# uJOVE7.net
KiCad netlist of a schematic drawn in EAGLE
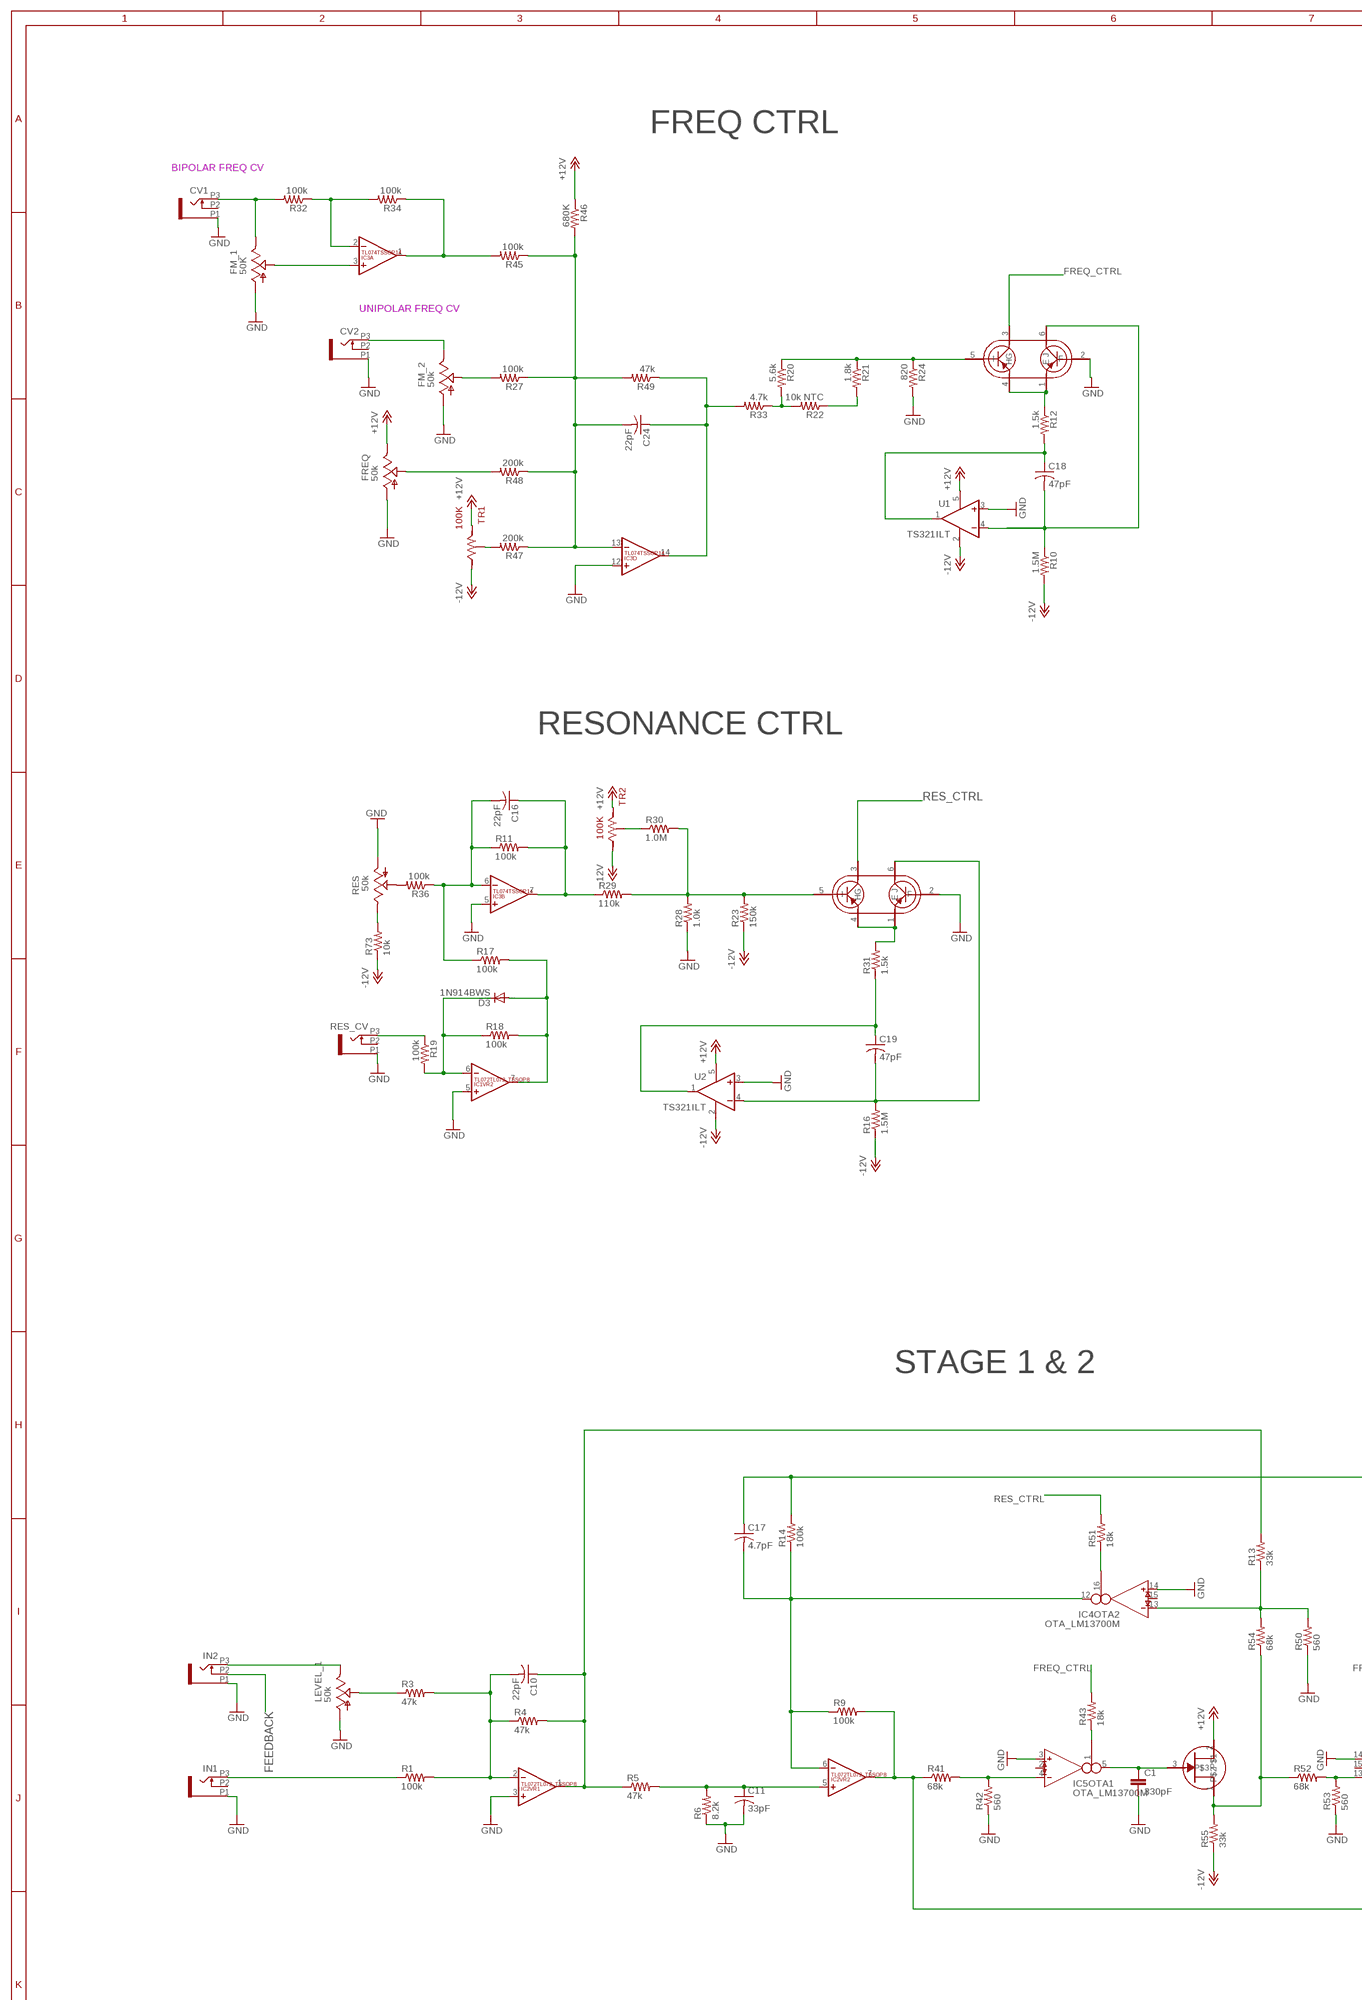
[diagram p0: schematic, sheet 1, part 1 of 3]
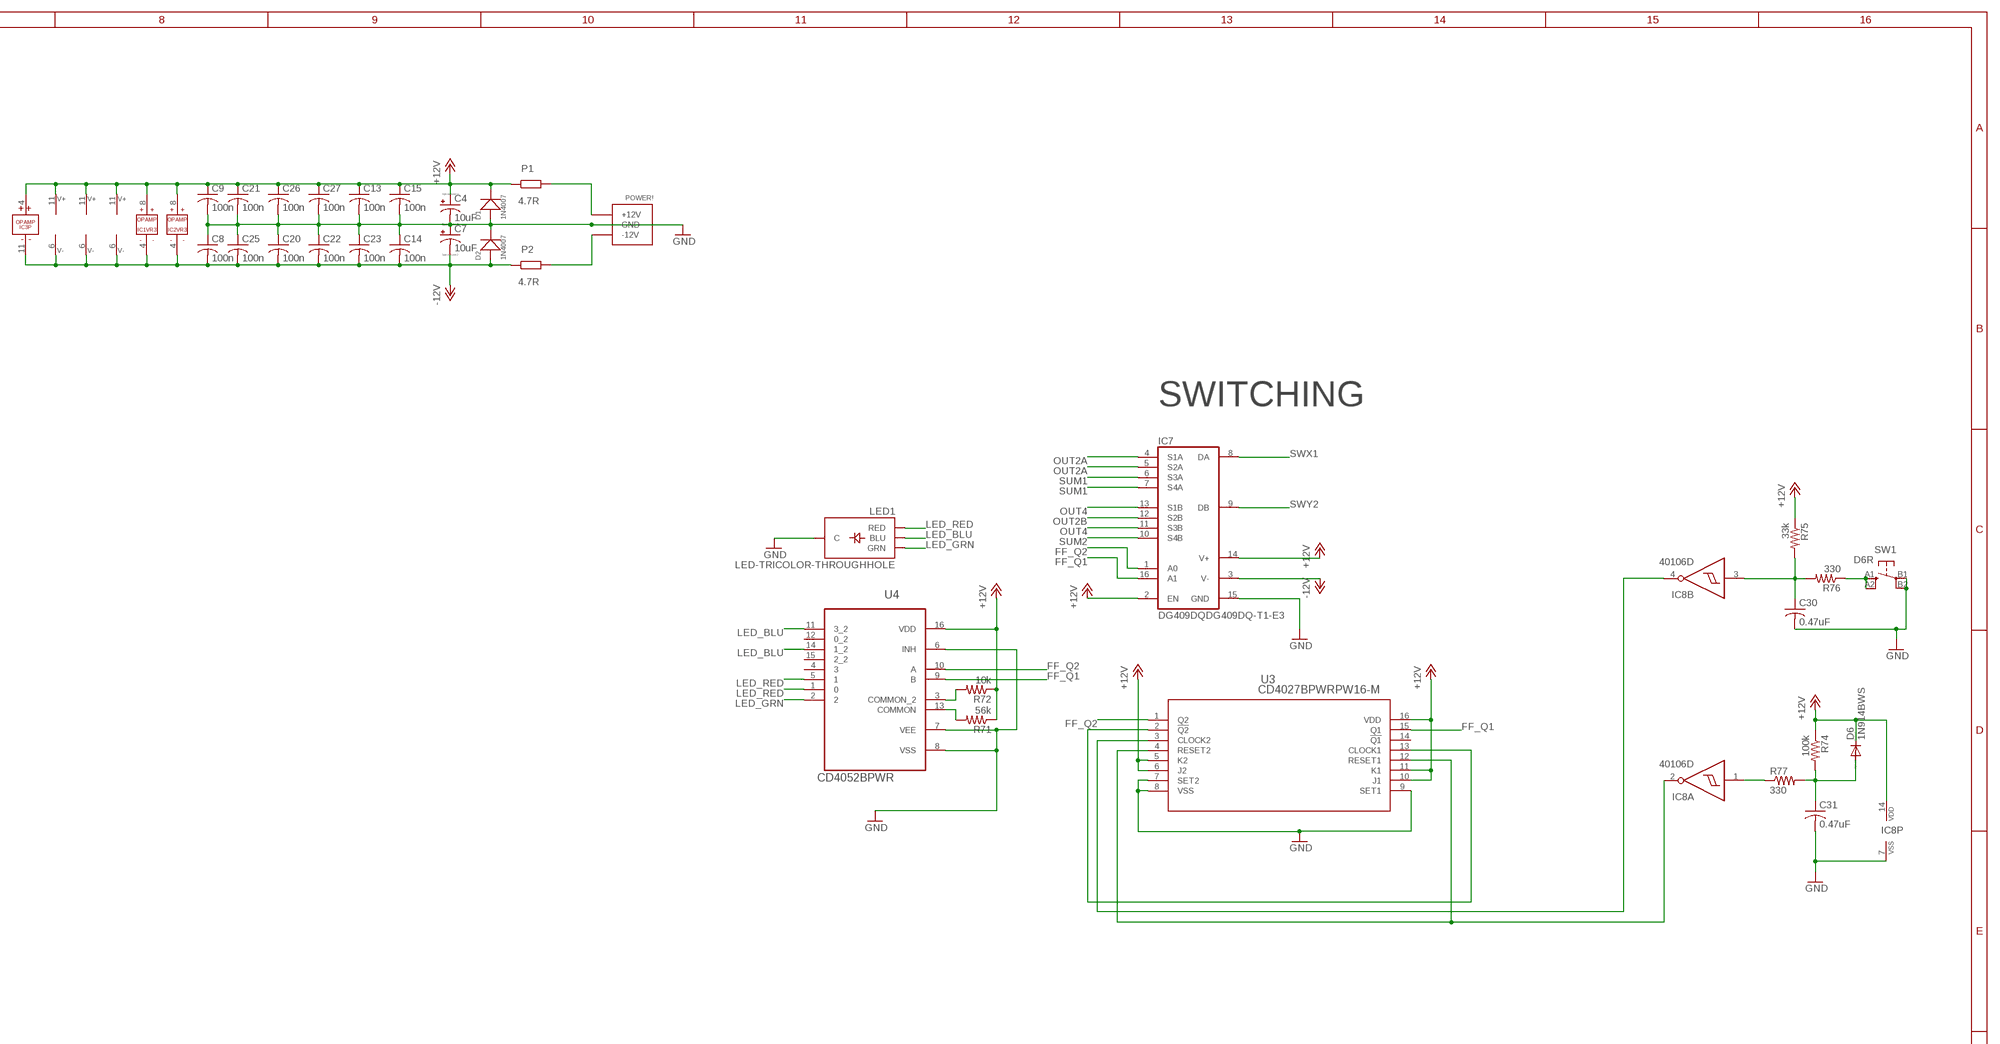
[diagram p1: schematic, sheet 1, part 2 of 3]
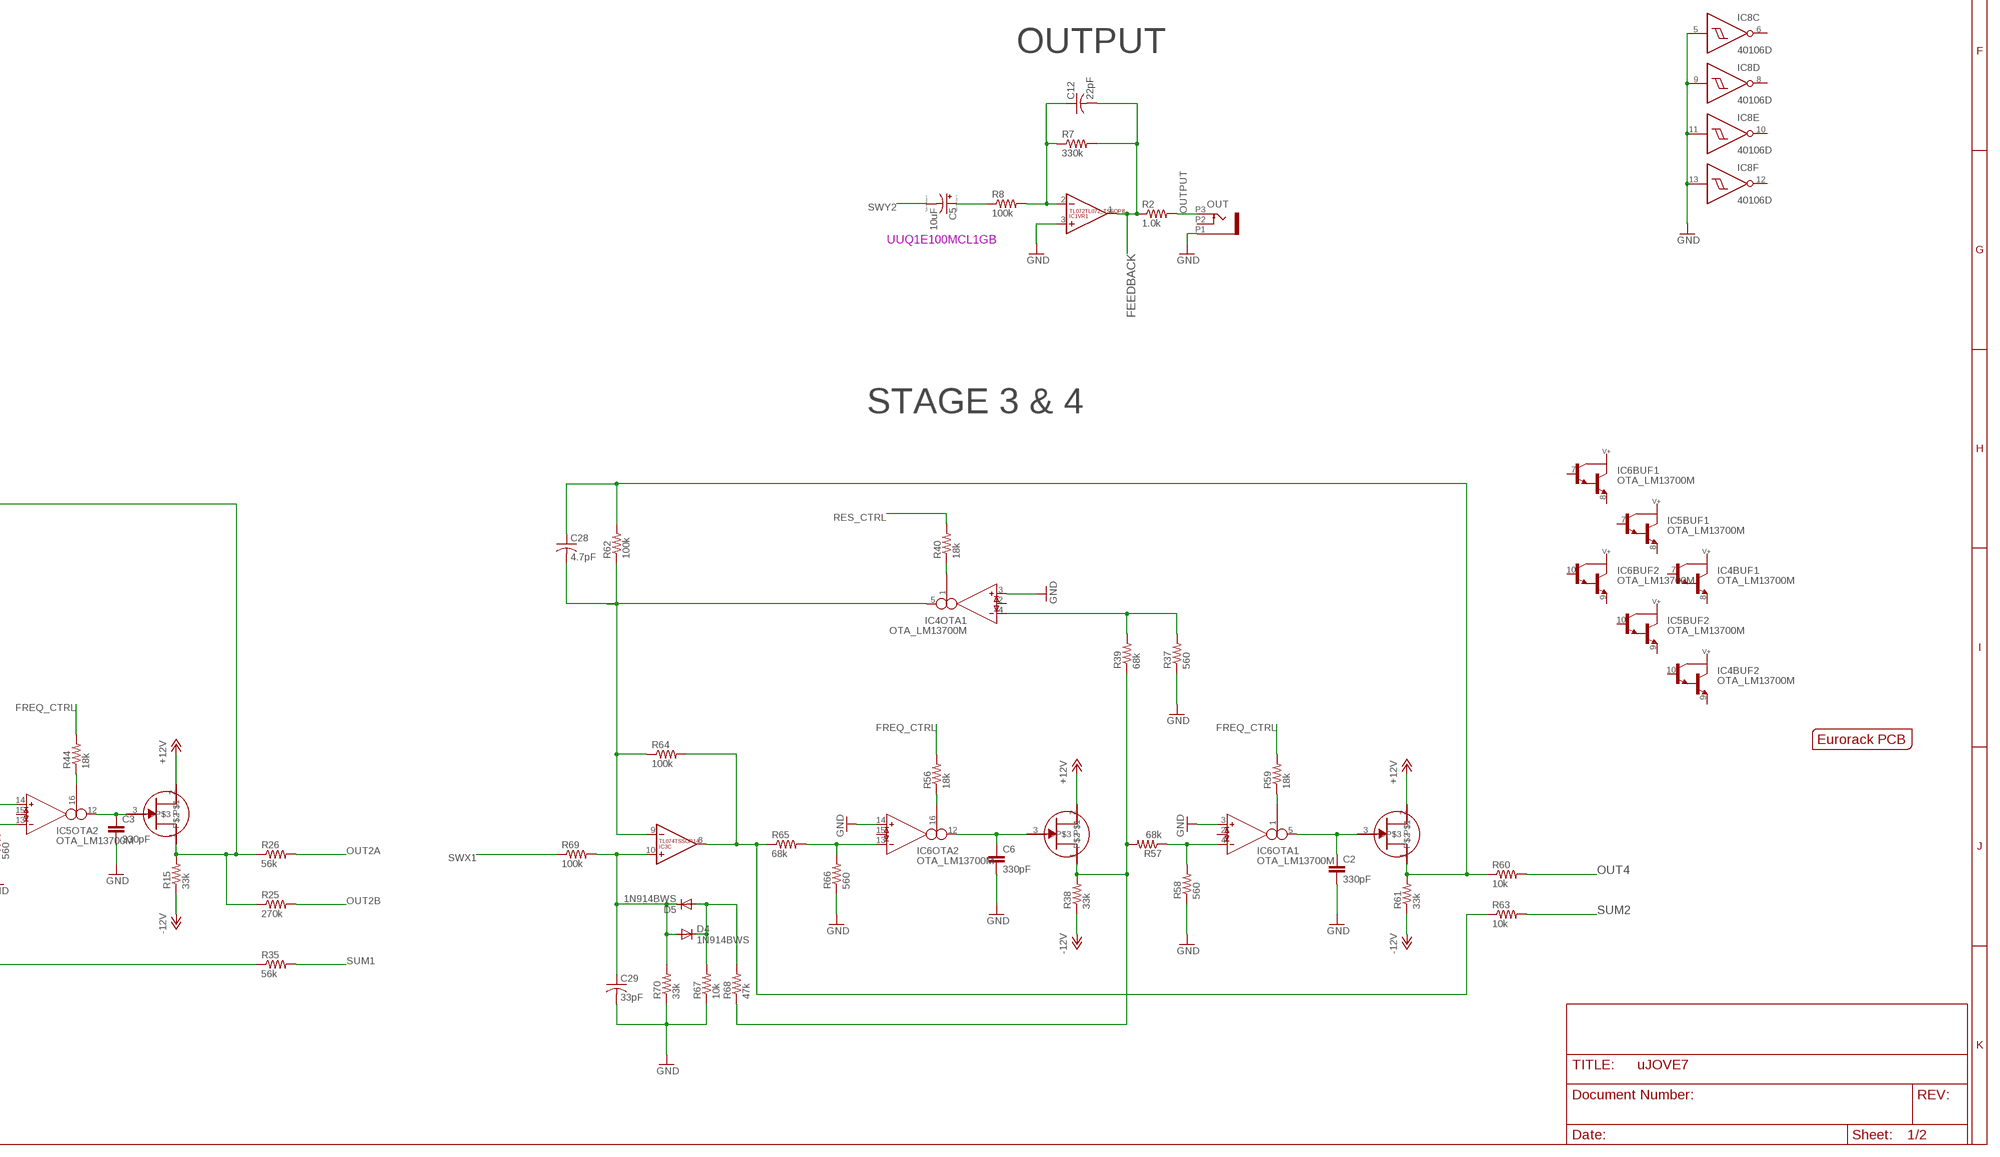
[diagram p2: schematic, sheet 1, part 3 of 3]

(export (version "E")
  (design (tool "Eeschema 10.0.6"))
  (components
    (comp (ref "C1")
      (value "330pF")
      (footprint "eagle-import:C5B5")
      (libsource (lib "eagle-import") (part "C5/5"))
    )
    (comp (ref "C2")
      (value "330pF")
      (footprint "eagle-import:C5B5")
      (libsource (lib "eagle-import") (part "C5/5"))
    )
    (comp (ref "C3")
      (value "330pF")
      (footprint "eagle-import:C5B5")
      (libsource (lib "eagle-import") (part "C5/5"))
    )
    (comp (ref "C4")
      (value "10uF")
      (footprint "eagle-import:PANASONIC_C")
      (libsource (lib "eagle-import") (part "CPOL-USC"))
    )
    (comp (ref "C5")
      (value "10uF")
      (footprint "eagle-import:PANASONIC_C")
      (libsource (lib "eagle-import") (part "CPOL-USC"))
    )
    (comp (ref "C6")
      (value "330pF")
      (footprint "eagle-import:C5B5")
      (libsource (lib "eagle-import") (part "C5/5"))
    )
    (comp (ref "C7")
      (value "10uF")
      (footprint "eagle-import:PANASONIC_C")
      (libsource (lib "eagle-import") (part "CPOL-USC"))
    )
    (comp (ref "C8")
      (value "100n")
      (footprint "eagle-import:C0603")
      (libsource (lib "eagle-import") (part "C-USC0603"))
    )
    (comp (ref "C9")
      (value "100n")
      (footprint "eagle-import:C0603")
      (libsource (lib "eagle-import") (part "C-USC0603"))
    )
    (comp (ref "C10")
      (value "22pF")
      (footprint "eagle-import:C0603")
      (libsource (lib "eagle-import") (part "C-USC0603"))
    )
    (comp (ref "C11")
      (value "33pF")
      (footprint "eagle-import:C0603")
      (libsource (lib "eagle-import") (part "C-USC0603"))
    )
    (comp (ref "C12")
      (value "22pF")
      (footprint "eagle-import:C0603")
      (libsource (lib "eagle-import") (part "C-USC0603"))
    )
    (comp (ref "C13")
      (value "100n")
      (footprint "eagle-import:C0603")
      (libsource (lib "eagle-import") (part "C-USC0603"))
    )
    (comp (ref "C14")
      (value "100n")
      (footprint "eagle-import:C0603")
      (libsource (lib "eagle-import") (part "C-USC0603"))
    )
    (comp (ref "C15")
      (value "100n")
      (footprint "eagle-import:C0603")
      (libsource (lib "eagle-import") (part "C-USC0603"))
    )
    (comp (ref "C16")
      (value "22pF")
      (footprint "eagle-import:C0603")
      (libsource (lib "eagle-import") (part "C-USC0603"))
    )
    (comp (ref "C17")
      (value "4.7pF")
      (footprint "eagle-import:C0603")
      (libsource (lib "eagle-import") (part "C-USC0603"))
    )
    (comp (ref "C18")
      (value "47pF")
      (footprint "eagle-import:C0603")
      (libsource (lib "eagle-import") (part "C-USC0603"))
    )
    (comp (ref "C19")
      (value "47pF")
      (footprint "eagle-import:C0603")
      (libsource (lib "eagle-import") (part "C-USC0603"))
    )
    (comp (ref "C20")
      (value "100n")
      (footprint "eagle-import:C0603")
      (libsource (lib "eagle-import") (part "C-USC0603"))
    )
    (comp (ref "C21")
      (value "100n")
      (footprint "eagle-import:C0603")
      (libsource (lib "eagle-import") (part "C-USC0603"))
    )
    (comp (ref "C22")
      (value "100n")
      (footprint "eagle-import:C0603")
      (libsource (lib "eagle-import") (part "C-USC0603"))
    )
    (comp (ref "C23")
      (value "100n")
      (footprint "eagle-import:C0603")
      (libsource (lib "eagle-import") (part "C-USC0603"))
    )
    (comp (ref "C24")
      (value "22pF")
      (footprint "eagle-import:C0603")
      (libsource (lib "eagle-import") (part "C-USC0603"))
    )
    (comp (ref "C25")
      (value "100n")
      (footprint "eagle-import:C0603")
      (libsource (lib "eagle-import") (part "C-USC0603"))
    )
    (comp (ref "C26")
      (value "100n")
      (footprint "eagle-import:C0603")
      (libsource (lib "eagle-import") (part "C-USC0603"))
    )
    (comp (ref "C27")
      (value "100n")
      (footprint "eagle-import:C0603")
      (libsource (lib "eagle-import") (part "C-USC0603"))
    )
    (comp (ref "C28")
      (value "4.7pF")
      (footprint "eagle-import:C0603")
      (libsource (lib "eagle-import") (part "C-USC0603"))
    )
    (comp (ref "C29")
      (value "33pF")
      (footprint "eagle-import:C0603")
      (libsource (lib "eagle-import") (part "C-USC0603"))
    )
    (comp (ref "C30")
      (value "0.47uF")
      (footprint "eagle-import:C0603")
      (libsource (lib "eagle-import") (part "C-USC0603"))
    )
    (comp (ref "C31")
      (value "0.47uF")
      (footprint "eagle-import:C0603")
      (libsource (lib "eagle-import") (part "C-USC0603"))
    )
    (comp (ref "CV1")
      (value "OG-PJ301_PJ301_THONKICONN")
      (footprint "eagle-import:OG-PJ301_WQP_PJ_301M6_NO_HOLE")
      (libsource (lib "eagle-import") (part "OG-PJ301_PJ301_THONKICONN"))
    )
    (comp (ref "CV2")
      (value "OG-PJ301_PJ301_THONKICONN")
      (footprint "eagle-import:OG-PJ301_WQP_PJ_301M6_NO_HOLE")
      (libsource (lib "eagle-import") (part "OG-PJ301_PJ301_THONKICONN"))
    )
    (comp (ref "D1")
      (value "1N4007")
      (footprint "eagle-import:DO-214AC")
      (libsource (lib "eagle-import") (part "DIODE-GEN-PURPOSE-1KV-1A(DO-214AC)"))
    )
    (comp (ref "D2")
      (value "1N4007")
      (footprint "eagle-import:DO-214AC")
      (libsource (lib "eagle-import") (part "DIODE-GEN-PURPOSE-1KV-1A(DO-214AC)"))
    )
    (comp (ref "D3")
      (value "1N914BWS")
      (footprint "eagle-import:SOD323-R")
      (libsource (lib "eagle-import") (part "DIODE-SOD323-R"))
    )
    (comp (ref "D4")
      (value "1N914BWS")
      (footprint "eagle-import:SOD323-R")
      (libsource (lib "eagle-import") (part "DIODE-SOD323-R"))
    )
    (comp (ref "D5")
      (value "1N914BWS")
      (footprint "eagle-import:SOD323-R")
      (libsource (lib "eagle-import") (part "DIODE-SOD323-R"))
    )
    (comp (ref "D6")
      (value "1N914BWS")
      (footprint "eagle-import:SOD323-R")
      (libsource (lib "eagle-import") (part "DIODE-SOD323-R"))
    )
    (comp (ref "FM_1")
      (value "50K")
      (footprint "eagle-import:OG-POTS_ALPS_POT_VERTICAL")
      (libsource (lib "eagle-import") (part "OG-POTS_POT_USVERTICAL"))
    )
    (comp (ref "FM_2")
      (value "50k")
      (footprint "eagle-import:OG-POTS_ALPS_POT_VERTICAL")
      (libsource (lib "eagle-import") (part "OG-POTS_POT_USVERTICAL"))
    )
    (comp (ref "FREQ")
      (value "50k")
      (footprint "eagle-import:OG-POTS_ALPS_POT_VERTICAL_PS")
      (libsource (lib "eagle-import") (part "OG-POTS_POT_USVERTICAL_PS"))
    )
    (comp (ref "IC1")
      (value "TL072TL072_TSSOP8")
      (footprint "eagle-import:TL072_TSSOP8")
      (libsource (lib "eagle-import") (part "TL072TL072_TSSOP8"))
    )
    (comp (ref "IC2")
      (value "TL072TL072_TSSOP8")
      (footprint "eagle-import:TL072_TSSOP8")
      (libsource (lib "eagle-import") (part "TL072TL072_TSSOP8"))
    )
    (comp (ref "IC3")
      (value "TL074TSSOP14")
      (footprint "eagle-import:TSSOP14")
      (libsource (lib "eagle-import") (part "TL074TSSOP14"))
    )
    (comp (ref "IC4")
      (value "OTA_LM13700M")
      (footprint "eagle-import:OTA_SO16")
      (libsource (lib "eagle-import") (part "OTA_LM13700M"))
    )
    (comp (ref "IC5")
      (value "OTA_LM13700M")
      (footprint "eagle-import:OTA_SO16")
      (libsource (lib "eagle-import") (part "OTA_LM13700M"))
    )
    (comp (ref "IC6")
      (value "OTA_LM13700M")
      (footprint "eagle-import:OTA_SO16")
      (libsource (lib "eagle-import") (part "OTA_LM13700M"))
    )
    (comp (ref "IC7")
      (value "DG409DQDG409DQ-T1-E3")
      (footprint "eagle-import:TSSOP16")
      (libsource (lib "eagle-import") (part "DG409DQDG409DQ-T1-E3"))
    )
    (comp (ref "IC8")
      (value "40106D")
      (footprint "eagle-import:SO14")
      (libsource (lib "eagle-import") (part "40106D"))
    )
    (comp (ref "IN1")
      (value "OG-PJ301_PJ301_THONKICONN")
      (footprint "eagle-import:OG-PJ301_WQP_PJ_301M6_NO_HOLE")
      (libsource (lib "eagle-import") (part "OG-PJ301_PJ301_THONKICONN"))
    )
    (comp (ref "IN2")
      (value "OG-PJ301_PJ301_THONKICONN")
      (footprint "eagle-import:OG-PJ301_WQP_PJ_301M6_NO_HOLE")
      (libsource (lib "eagle-import") (part "OG-PJ301_PJ301_THONKICONN"))
    )
    (comp (ref "LED1")
      (value "LED-TRICOLOR-THROUGHHOLE")
      (footprint "eagle-import:LED-TRICOLOR-THROUGHHOLE")
      (libsource (lib "eagle-import") (part "LED-TRICOLOR-THROUGHHOLE"))
    )
    (comp (ref "LEVEL_1")
      (value "50k")
      (footprint "eagle-import:OG-POTS_ALPS_POT_VERTICAL")
      (libsource (lib "eagle-import") (part "OG-POTS_POT_USVERTICAL"))
    )
    (comp (ref "OUT")
      (value "OG-PJ301_PJ301_THONKICONN")
      (footprint "eagle-import:OG-PJ301_WQP_PJ_301M6_NO_HOLE")
      (libsource (lib "eagle-import") (part "OG-PJ301_PJ301_THONKICONN"))
    )
    (comp (ref "P1")
      (value "4.7R")
      (footprint "eagle-import:R1206")
      (libsource (lib "eagle-import") (part "R-EU_R1206"))
    )
    (comp (ref "P2")
      (value "4.7R")
      (footprint "eagle-import:R1206")
      (libsource (lib "eagle-import") (part "R-EU_R1206"))
    )
    (comp (ref "PCB1")
      (value "EURORACK_PCB")
      (footprint "eagle-import:EURORACK8HPPCB-S")
      (libsource (lib "eagle-import") (part "EURORACK_PCB"))
    )
    (comp (ref "POWER!")
      (value "POWER_SIMPLE")
      (footprint "eagle-import:2X05_SMT_HEADER")
      (libsource (lib "eagle-import") (part "POWER_SIMPLE"))
    )
    (comp (ref "Q1")
      (value "BCM857BS")
      (footprint "eagle-import:SOT65P210X110-6N")
      (libsource (lib "eagle-import") (part "BCM857BS"))
    )
    (comp (ref "Q2")
      (value "BCM857BS")
      (footprint "eagle-import:SOT65P210X110-6N")
      (libsource (lib "eagle-import") (part "BCM857BS"))
    )
    (comp (ref "Q3")
      (value "MMBFJ112MMBFJ112")
      (footprint "eagle-import:SOT23")
      (libsource (lib "eagle-import") (part "MMBFJ112MMBFJ112"))
    )
    (comp (ref "Q4")
      (value "MMBFJ112MMBFJ112")
      (footprint "eagle-import:SOT23")
      (libsource (lib "eagle-import") (part "MMBFJ112MMBFJ112"))
    )
    (comp (ref "Q5")
      (value "MMBFJ112MMBFJ112")
      (footprint "eagle-import:SOT23")
      (libsource (lib "eagle-import") (part "MMBFJ112MMBFJ112"))
    )
    (comp (ref "Q6")
      (value "MMBFJ112MMBFJ112")
      (footprint "eagle-import:SOT23")
      (libsource (lib "eagle-import") (part "MMBFJ112MMBFJ112"))
    )
    (comp (ref "R1")
      (value "100k")
      (footprint "eagle-import:R0603")
      (libsource (lib "eagle-import") (part "R-US_R0603"))
    )
    (comp (ref "R2")
      (value "1.0k")
      (footprint "eagle-import:R0603")
      (libsource (lib "eagle-import") (part "R-US_R0603"))
    )
    (comp (ref "R3")
      (value "47k")
      (footprint "eagle-import:R0603")
      (libsource (lib "eagle-import") (part "R-US_R0603"))
    )
    (comp (ref "R4")
      (value "47k")
      (footprint "eagle-import:R0603")
      (libsource (lib "eagle-import") (part "R-US_R0603"))
    )
    (comp (ref "R5")
      (value "47k")
      (footprint "eagle-import:R0603")
      (libsource (lib "eagle-import") (part "R-US_R0603"))
    )
    (comp (ref "R6")
      (value "8.2k")
      (footprint "eagle-import:R0603")
      (libsource (lib "eagle-import") (part "R-US_R0603"))
    )
    (comp (ref "R7")
      (value "330k")
      (footprint "eagle-import:R0603")
      (libsource (lib "eagle-import") (part "R-US_R0603"))
    )
    (comp (ref "R8")
      (value "100k")
      (footprint "eagle-import:R0603")
      (libsource (lib "eagle-import") (part "R-US_R0603"))
    )
    (comp (ref "R9")
      (value "100k")
      (footprint "eagle-import:R0603")
      (libsource (lib "eagle-import") (part "R-US_R0603"))
    )
    (comp (ref "R10")
      (value "1.5M")
      (footprint "eagle-import:R0603")
      (libsource (lib "eagle-import") (part "R-US_R0603"))
    )
    (comp (ref "R11")
      (value "100k")
      (footprint "eagle-import:R0603")
      (libsource (lib "eagle-import") (part "R-US_R0603"))
    )
    (comp (ref "R12")
      (value "1.5k")
      (footprint "eagle-import:R0603")
      (libsource (lib "eagle-import") (part "R-US_R0603"))
    )
    (comp (ref "R13")
      (value "33k")
      (footprint "eagle-import:R0603")
      (libsource (lib "eagle-import") (part "R-US_R0603"))
    )
    (comp (ref "R14")
      (value "100k")
      (footprint "eagle-import:R0603")
      (libsource (lib "eagle-import") (part "R-US_R0603"))
    )
    (comp (ref "R15")
      (value "33k")
      (footprint "eagle-import:R0603")
      (libsource (lib "eagle-import") (part "R-US_R0603"))
    )
    (comp (ref "R16")
      (value "1.5M")
      (footprint "eagle-import:R0603")
      (libsource (lib "eagle-import") (part "R-US_R0603"))
    )
    (comp (ref "R17")
      (value "100k")
      (footprint "eagle-import:R0603")
      (libsource (lib "eagle-import") (part "R-US_R0603"))
    )
    (comp (ref "R18")
      (value "100k")
      (footprint "eagle-import:R0603")
      (libsource (lib "eagle-import") (part "R-US_R0603"))
    )
    (comp (ref "R19")
      (value "100k")
      (footprint "eagle-import:R0603")
      (libsource (lib "eagle-import") (part "R-US_R0603"))
    )
    (comp (ref "R20")
      (value "5.6k")
      (footprint "eagle-import:R0603")
      (libsource (lib "eagle-import") (part "R-US_R0603"))
    )
    (comp (ref "R21")
      (value "1.8k")
      (footprint "eagle-import:R0603")
      (libsource (lib "eagle-import") (part "R-US_R0603"))
    )
    (comp (ref "R22")
      (value "10k NTC")
      (footprint "eagle-import:R0805")
      (libsource (lib "eagle-import") (part "resistor_348_R-US_R0805"))
    )
    (comp (ref "R23")
      (value "150k")
      (footprint "eagle-import:R0603")
      (libsource (lib "eagle-import") (part "R-US_R0603"))
    )
    (comp (ref "R24")
      (value "820")
      (footprint "eagle-import:R0603")
      (libsource (lib "eagle-import") (part "R-US_R0603"))
    )
    (comp (ref "R25")
      (value "270k")
      (footprint "eagle-import:R0603")
      (libsource (lib "eagle-import") (part "R-US_R0603"))
    )
    (comp (ref "R26")
      (value "56k")
      (footprint "eagle-import:R0603")
      (libsource (lib "eagle-import") (part "R-US_R0603"))
    )
    (comp (ref "R27")
      (value "100k")
      (footprint "eagle-import:R0603")
      (libsource (lib "eagle-import") (part "R-US_R0603"))
    )
    (comp (ref "R28")
      (value "1.0k")
      (footprint "eagle-import:R0603")
      (libsource (lib "eagle-import") (part "R-US_R0603"))
    )
    (comp (ref "R29")
      (value "110k")
      (footprint "eagle-import:R0603")
      (libsource (lib "eagle-import") (part "R-US_R0603"))
    )
    (comp (ref "R30")
      (value "1.0M")
      (footprint "eagle-import:R0603")
      (libsource (lib "eagle-import") (part "R-US_R0603"))
    )
    (comp (ref "R31")
      (value "1.5k")
      (footprint "eagle-import:R0603")
      (libsource (lib "eagle-import") (part "R-US_R0603"))
    )
    (comp (ref "R32")
      (value "100k")
      (footprint "eagle-import:R0603")
      (libsource (lib "eagle-import") (part "R-US_R0603"))
    )
    (comp (ref "R33")
      (value "4.7k")
      (footprint "eagle-import:R0603")
      (libsource (lib "eagle-import") (part "R-US_R0603"))
    )
    (comp (ref "R34")
      (value "100k")
      (footprint "eagle-import:R0603")
      (libsource (lib "eagle-import") (part "R-US_R0603"))
    )
    (comp (ref "R35")
      (value "56k")
      (footprint "eagle-import:R0603")
      (libsource (lib "eagle-import") (part "R-US_R0603"))
    )
    (comp (ref "R36")
      (value "100k")
      (footprint "eagle-import:R0603")
      (libsource (lib "eagle-import") (part "R-US_R0603"))
    )
    (comp (ref "R37")
      (value "560")
      (footprint "eagle-import:R0603")
      (libsource (lib "eagle-import") (part "R-US_R0603"))
    )
    (comp (ref "R38")
      (value "33k")
      (footprint "eagle-import:R0603")
      (libsource (lib "eagle-import") (part "R-US_R0603"))
    )
    (comp (ref "R39")
      (value "68k")
      (footprint "eagle-import:R0603")
      (libsource (lib "eagle-import") (part "R-US_R0603"))
    )
    (comp (ref "R40")
      (value "18k")
      (footprint "eagle-import:R0603")
      (libsource (lib "eagle-import") (part "R-US_R0603"))
    )
    (comp (ref "R41")
      (value "68k")
      (footprint "eagle-import:R0603")
      (libsource (lib "eagle-import") (part "R-US_R0603"))
    )
    (comp (ref "R42")
      (value "560")
      (footprint "eagle-import:R0603")
      (libsource (lib "eagle-import") (part "R-US_R0603"))
    )
    (comp (ref "R43")
      (value "18k")
      (footprint "eagle-import:R0603")
      (libsource (lib "eagle-import") (part "R-US_R0603"))
    )
    (comp (ref "R44")
      (value "18k")
      (footprint "eagle-import:R0603")
      (libsource (lib "eagle-import") (part "R-US_R0603"))
    )
    (comp (ref "R45")
      (value "100k")
      (footprint "eagle-import:R0603")
      (libsource (lib "eagle-import") (part "R-US_R0603"))
    )
    (comp (ref "R46")
      (value "680K")
      (footprint "eagle-import:R0603")
      (libsource (lib "eagle-import") (part "R-US_R0603"))
    )
    (comp (ref "R47")
      (value "200k")
      (footprint "eagle-import:R0603")
      (libsource (lib "eagle-import") (part "R-US_R0603"))
    )
    (comp (ref "R48")
      (value "200k")
      (footprint "eagle-import:R0603")
      (libsource (lib "eagle-import") (part "R-US_R0603"))
    )
    (comp (ref "R49")
      (value "47k")
      (footprint "eagle-import:R0603")
      (libsource (lib "eagle-import") (part "R-US_R0603"))
    )
    (comp (ref "R50")
      (value "560")
      (footprint "eagle-import:R0603")
      (libsource (lib "eagle-import") (part "R-US_R0603"))
    )
    (comp (ref "R51")
      (value "18k")
      (footprint "eagle-import:R0603")
      (libsource (lib "eagle-import") (part "R-US_R0603"))
    )
    (comp (ref "R52")
      (value "68k")
      (footprint "eagle-import:R0603")
      (libsource (lib "eagle-import") (part "R-US_R0603"))
    )
    (comp (ref "R53")
      (value "560")
      (footprint "eagle-import:R0603")
      (libsource (lib "eagle-import") (part "R-US_R0603"))
    )
    (comp (ref "R54")
      (value "68k")
      (footprint "eagle-import:R0603")
      (libsource (lib "eagle-import") (part "R-US_R0603"))
    )
    (comp (ref "R55")
      (value "33k")
      (footprint "eagle-import:R0603")
      (libsource (lib "eagle-import") (part "R-US_R0603"))
    )
    (comp (ref "R56")
      (value "18k")
      (footprint "eagle-import:R0603")
      (libsource (lib "eagle-import") (part "R-US_R0603"))
    )
    (comp (ref "R57")
      (value "68k")
      (footprint "eagle-import:R0603")
      (libsource (lib "eagle-import") (part "R-US_R0603"))
    )
    (comp (ref "R58")
      (value "560")
      (footprint "eagle-import:R0603")
      (libsource (lib "eagle-import") (part "R-US_R0603"))
    )
    (comp (ref "R59")
      (value "18k")
      (footprint "eagle-import:R0603")
      (libsource (lib "eagle-import") (part "R-US_R0603"))
    )
    (comp (ref "R60")
      (value "10k")
      (footprint "eagle-import:R0603")
      (libsource (lib "eagle-import") (part "R-US_R0603"))
    )
    (comp (ref "R61")
      (value "33k")
      (footprint "eagle-import:R0603")
      (libsource (lib "eagle-import") (part "R-US_R0603"))
    )
    (comp (ref "R62")
      (value "100k")
      (footprint "eagle-import:R0603")
      (libsource (lib "eagle-import") (part "R-US_R0603"))
    )
    (comp (ref "R63")
      (value "10k")
      (footprint "eagle-import:R0603")
      (libsource (lib "eagle-import") (part "R-US_R0603"))
    )
    (comp (ref "R64")
      (value "100k")
      (footprint "eagle-import:R0603")
      (libsource (lib "eagle-import") (part "R-US_R0603"))
    )
    (comp (ref "R65")
      (value "68k")
      (footprint "eagle-import:R0603")
      (libsource (lib "eagle-import") (part "R-US_R0603"))
    )
    (comp (ref "R66")
      (value "560")
      (footprint "eagle-import:R0603")
      (libsource (lib "eagle-import") (part "R-US_R0603"))
    )
    (comp (ref "R67")
      (value "10k")
      (footprint "eagle-import:R0603")
      (libsource (lib "eagle-import") (part "R-US_R0603"))
    )
    (comp (ref "R68")
      (value "47k")
      (footprint "eagle-import:R0603")
      (libsource (lib "eagle-import") (part "R-US_R0603"))
    )
    (comp (ref "R69")
      (value "100k")
      (footprint "eagle-import:R0603")
      (libsource (lib "eagle-import") (part "R-US_R0603"))
    )
    (comp (ref "R70")
      (value "33k")
      (footprint "eagle-import:R0603")
      (libsource (lib "eagle-import") (part "R-US_R0603"))
    )
    (comp (ref "R71")
      (value "56k")
      (footprint "eagle-import:R0603")
      (libsource (lib "eagle-import") (part "R-US_R0603"))
    )
    (comp (ref "R72")
      (value "10k")
      (footprint "eagle-import:R0603")
      (libsource (lib "eagle-import") (part "R-US_R0603"))
    )
    (comp (ref "R73")
      (value "10k")
      (footprint "eagle-import:R0603")
      (libsource (lib "eagle-import") (part "R-US_R0603"))
    )
    (comp (ref "R74")
      (value "100k")
      (footprint "eagle-import:R0603")
      (libsource (lib "eagle-import") (part "R-US_R0603"))
    )
    (comp (ref "R75")
      (value "33k")
      (footprint "eagle-import:R0603")
      (libsource (lib "eagle-import") (part "R-US_R0603"))
    )
    (comp (ref "R76")
      (value "330")
      (footprint "eagle-import:R0603")
      (libsource (lib "eagle-import") (part "R-US_R0603"))
    )
    (comp (ref "R77")
      (value "330")
      (footprint "eagle-import:R0603")
      (libsource (lib "eagle-import") (part "R-US_R0603"))
    )
    (comp (ref "RES")
      (value "50k")
      (footprint "eagle-import:OG-POTS_ALPS_POT_VERTICAL_PS")
      (libsource (lib "eagle-import") (part "OG-POTS_POT_USVERTICAL_PS"))
    )
    (comp (ref "RES_CV")
      (value "OG-PJ301_PJ301_THONKICONN")
      (footprint "eagle-import:OG-PJ301_WQP_PJ_301M6_NO_HOLE")
      (libsource (lib "eagle-import") (part "OG-PJ301_PJ301_THONKICONN"))
    )
    (comp (ref "SW1")
      (value "D6R")
      (footprint "eagle-import:D6R")
      (libsource (lib "eagle-import") (part "D6R"))
    )
    (comp (ref "TR1")
      (value "100K")
      (footprint "eagle-import:TC33X-2")
      (fields (field (name "ARROW_PART_NUMBER") "TC33X-2-104E") (field (name "RS_PART_NUMBER") "1673550"))
      (libsource (lib "eagle-import") (part "TC33X-2-104E"))
    )
    (comp (ref "TR2")
      (value "100K")
      (footprint "eagle-import:TC33X-2")
      (fields (field (name "ARROW_PART_NUMBER") "TC33X-2-104E") (field (name "RS_PART_NUMBER") "1673550"))
      (libsource (lib "eagle-import") (part "TC33X-2-104E"))
    )
    (comp (ref "U1")
      (value "TS321ILT")
      (footprint "eagle-import:SOT23-5")
      (fields (field (name "MF") "STMicroelectronics") (field (name "MP") "TS321I"))
      (libsource (lib "eagle-import") (part "TS321IDBV"))
    )
    (comp (ref "U2")
      (value "TS321ILT")
      (footprint "eagle-import:SOT23-5")
      (fields (field (name "MF") "STMicroelectronics") (field (name "MP") "TS321I"))
      (libsource (lib "eagle-import") (part "TS321IDBV"))
    )
    (comp (ref "U3")
      (value "CD4027BPWRPW16-M")
      (footprint "eagle-import:PW16-M")
      (fields (field (name "MANUFACTURER_PART_NUMBER") "CD4027BPWR"))
      (libsource (lib "eagle-import") (part "CD4027BPWRPW16-M"))
    )
    (comp (ref "U4")
      (value "CD4052BPWR")
      (footprint "eagle-import:SOP65P640X120-16N")
      (fields (field (name "MF") "Texas Instruments"))
      (libsource (lib "eagle-import") (part "CD4052BPWR"))
    )
  )
  (nets
    (net (code "1") (name "+12V") (class "Default")
      (node (ref "C13") (pin "1") (pinfunction "1_1") (pintype "passive"))
      (node (ref "C15") (pin "1") (pinfunction "1_1") (pintype "passive"))
      (node (ref "C21") (pin "1") (pinfunction "1_1") (pintype "passive"))
      (node (ref "C26") (pin "1") (pinfunction "1_1") (pintype "passive"))
      (node (ref "C27") (pin "1") (pinfunction "1_1") (pintype "passive"))
      (node (ref "C4") (pin "+") (pinfunction "+_+") (pintype "passive"))
      (node (ref "C9") (pin "1") (pinfunction "1_1") (pintype "passive"))
      (node (ref "D1") (pin "2") (pinfunction "-_2") (pintype "passive"))
      (node (ref "D6") (pin "C") (pinfunction "C_C") (pintype "passive"))
      (node (ref "FREQ") (pin "P$1") (pinfunction "E_P$1") (pintype "passive"))
      (node (ref "IC1") (pin "8") (pinfunction "V+_8") (pintype "power_in"))
      (node (ref "IC2") (pin "8") (pinfunction "V+_8") (pintype "power_in"))
      (node (ref "IC3") (pin "4") (pinfunction "V+_4") (pintype "power_in"))
      (node (ref "IC4") (pin "11") (pinfunction "V+_11") (pintype "power_in"))
      (node (ref "IC5") (pin "11") (pinfunction "V+_11") (pintype "power_in"))
      (node (ref "IC6") (pin "11") (pinfunction "V+_11") (pintype "power_in"))
      (node (ref "IC7") (pin "14") (pinfunction "V+_14") (pintype "power_in"))
      (node (ref "IC7") (pin "2") (pinfunction "EN_2") (pintype "input"))
      (node (ref "IC8") (pin "14") (pinfunction "VDD_14") (pintype "power_in"))
      (node (ref "P1") (pin "1") (pinfunction "1_1") (pintype "passive"))
      (node (ref "Q3") (pin "2") (pinfunction "P$2_2") (pintype "bidirectional"))
      (node (ref "Q4") (pin "2") (pinfunction "P$2_2") (pintype "bidirectional"))
      (node (ref "Q5") (pin "2") (pinfunction "P$2_2") (pintype "bidirectional"))
      (node (ref "Q6") (pin "2") (pinfunction "P$2_2") (pintype "bidirectional"))
      (node (ref "R46") (pin "1") (pinfunction "1_1") (pintype "passive"))
      (node (ref "R71") (pin "1") (pinfunction "1_1") (pintype "passive"))
      (node (ref "R72") (pin "1") (pinfunction "1_1") (pintype "passive"))
      (node (ref "R74") (pin "1") (pinfunction "1_1") (pintype "passive"))
      (node (ref "R75") (pin "1") (pinfunction "1_1") (pintype "passive"))
      (node (ref "TR1") (pin "1") (pinfunction "P$1_1") (pintype "bidirectional"))
      (node (ref "TR2") (pin "1") (pinfunction "P$1_1") (pintype "bidirectional"))
      (node (ref "U1") (pin "5") (pinfunction "V+_5") (pintype "power_in"))
      (node (ref "U2") (pin "5") (pinfunction "V+_5") (pintype "power_in"))
      (node (ref "U3") (pin "10") (pinfunction "J1_10") (pintype "input"))
      (node (ref "U3") (pin "11") (pinfunction "K1_11") (pintype "input"))
      (node (ref "U3") (pin "16") (pinfunction "VDD_16") (pintype "power_in"))
      (node (ref "U3") (pin "5") (pinfunction "K2_5") (pintype "input"))
      (node (ref "U3") (pin "6") (pinfunction "J2_6") (pintype "input"))
      (node (ref "U4") (pin "16") (pinfunction "VDD_16") (pintype "power_in"))
    )
    (net (code "2") (name "-12V") (class "Default")
      (node (ref "C14") (pin "2") (pinfunction "2_2") (pintype "passive"))
      (node (ref "C20") (pin "2") (pinfunction "2_2") (pintype "passive"))
      (node (ref "C22") (pin "2") (pinfunction "2_2") (pintype "passive"))
      (node (ref "C23") (pin "2") (pinfunction "2_2") (pintype "passive"))
      (node (ref "C25") (pin "2") (pinfunction "2_2") (pintype "passive"))
      (node (ref "C7") (pin "-") (pinfunction "-_-") (pintype "passive"))
      (node (ref "C8") (pin "2") (pinfunction "2_2") (pintype "passive"))
      (node (ref "D2") (pin "1") (pinfunction "+_1") (pintype "passive"))
      (node (ref "IC1") (pin "4") (pinfunction "V-_4") (pintype "power_in"))
      (node (ref "IC2") (pin "4") (pinfunction "V-_4") (pintype "power_in"))
      (node (ref "IC3") (pin "11") (pinfunction "V-_11") (pintype "power_in"))
      (node (ref "IC4") (pin "6") (pinfunction "V-_6") (pintype "power_in"))
      (node (ref "IC5") (pin "6") (pinfunction "V-_6") (pintype "power_in"))
      (node (ref "IC6") (pin "6") (pinfunction "V-_6") (pintype "power_in"))
      (node (ref "IC7") (pin "3") (pinfunction "V-_3") (pintype "power_in"))
      (node (ref "P2") (pin "1") (pinfunction "1_1") (pintype "passive"))
      (node (ref "R10") (pin "2") (pinfunction "2_2") (pintype "passive"))
      (node (ref "R15") (pin "1") (pinfunction "1_1") (pintype "passive"))
      (node (ref "R16") (pin "1") (pinfunction "1_1") (pintype "passive"))
      (node (ref "R23") (pin "1") (pinfunction "1_1") (pintype "passive"))
      (node (ref "R38") (pin "1") (pinfunction "1_1") (pintype "passive"))
      (node (ref "R55") (pin "1") (pinfunction "1_1") (pintype "passive"))
      (node (ref "R61") (pin "1") (pinfunction "1_1") (pintype "passive"))
      (node (ref "R73") (pin "1") (pinfunction "1_1") (pintype "passive"))
      (node (ref "TR1") (pin "3") (pinfunction "P$3_3") (pintype "bidirectional"))
      (node (ref "TR2") (pin "3") (pinfunction "P$3_3") (pintype "bidirectional"))
      (node (ref "U1") (pin "2") (pinfunction "V-_2") (pintype "power_in"))
      (node (ref "U2") (pin "2") (pinfunction "V-_2") (pintype "power_in"))
    )
    (net (code "3") (name "FEEDBACK") (class "Default")
      (node (ref "C12") (pin "2") (pinfunction "2_2") (pintype "passive"))
      (node (ref "IC1") (pin "1") (pinfunction "OUT_1") (pintype "output"))
      (node (ref "IN2") (pin "P2") (pinfunction "2_P2") (pintype "passive"))
      (node (ref "R2") (pin "1") (pinfunction "1_1") (pintype "passive"))
      (node (ref "R7") (pin "2") (pinfunction "2_2") (pintype "passive"))
    )
    (net (code "4") (name "FF_Q1") (class "Default")
      (node (ref "IC7") (pin "16") (pinfunction "A1_16") (pintype "input"))
      (node (ref "U3") (pin "15") (pinfunction "Q1_15") (pintype "output"))
      (node (ref "U4") (pin "9") (pinfunction "B_9") (pintype "input"))
    )
    (net (code "5") (name "FF_Q2") (class "Default")
      (node (ref "IC7") (pin "1") (pinfunction "A0_1") (pintype "input"))
      (node (ref "U3") (pin "1") (pinfunction "Q2_1") (pintype "output"))
      (node (ref "U4") (pin "10") (pinfunction "A_10") (pintype "input"))
    )
    (net (code "6") (name "FREQ_CTRL") (class "Default")
      (node (ref "Q1") (pin "3") (pinfunction "G_3") (pintype "bidirectional"))
      (node (ref "R43") (pin "2") (pinfunction "2_2") (pintype "passive"))
      (node (ref "R44") (pin "2") (pinfunction "2_2") (pintype "passive"))
      (node (ref "R56") (pin "2") (pinfunction "2_2") (pintype "passive"))
      (node (ref "R59") (pin "2") (pinfunction "2_2") (pintype "passive"))
    )
    (net (code "7") (name "GND") (class "Default")
      (node (ref "C1") (pin "2") (pinfunction "2_2") (pintype "passive"))
      (node (ref "C11") (pin "2") (pinfunction "2_2") (pintype "passive"))
      (node (ref "C13") (pin "2") (pinfunction "2_2") (pintype "passive"))
      (node (ref "C14") (pin "1") (pinfunction "1_1") (pintype "passive"))
      (node (ref "C15") (pin "2") (pinfunction "2_2") (pintype "passive"))
      (node (ref "C2") (pin "2") (pinfunction "2_2") (pintype "passive"))
      (node (ref "C20") (pin "1") (pinfunction "1_1") (pintype "passive"))
      (node (ref "C21") (pin "2") (pinfunction "2_2") (pintype "passive"))
      (node (ref "C22") (pin "1") (pinfunction "1_1") (pintype "passive"))
      (node (ref "C23") (pin "1") (pinfunction "1_1") (pintype "passive"))
      (node (ref "C25") (pin "1") (pinfunction "1_1") (pintype "passive"))
      (node (ref "C26") (pin "2") (pinfunction "2_2") (pintype "passive"))
      (node (ref "C27") (pin "2") (pinfunction "2_2") (pintype "passive"))
      (node (ref "C29") (pin "2") (pinfunction "2_2") (pintype "passive"))
      (node (ref "C3") (pin "2") (pinfunction "2_2") (pintype "passive"))
      (node (ref "C30") (pin "2") (pinfunction "2_2") (pintype "passive"))
      (node (ref "C31") (pin "2") (pinfunction "2_2") (pintype "passive"))
      (node (ref "C4") (pin "-") (pinfunction "-_-") (pintype "passive"))
      (node (ref "C6") (pin "2") (pinfunction "2_2") (pintype "passive"))
      (node (ref "C7") (pin "+") (pinfunction "+_+") (pintype "passive"))
      (node (ref "C8") (pin "1") (pinfunction "1_1") (pintype "passive"))
      (node (ref "C9") (pin "2") (pinfunction "2_2") (pintype "passive"))
      (node (ref "CV1") (pin "P1") (pinfunction "1_P1") (pintype "passive"))
      (node (ref "CV2") (pin "P1") (pinfunction "1_P1") (pintype "passive"))
      (node (ref "D1") (pin "1") (pinfunction "+_1") (pintype "passive"))
      (node (ref "D2") (pin "2") (pinfunction "-_2") (pintype "passive"))
      (node (ref "FM_1") (pin "P$3") (pinfunction "A_P$3") (pintype "passive"))
      (node (ref "FM_2") (pin "P$3") (pinfunction "A_P$3") (pintype "passive"))
      (node (ref "FREQ") (pin "P$3") (pinfunction "A_P$3") (pintype "passive"))
      (node (ref "IC1") (pin "3") (pinfunction "+IN_3") (pintype "input"))
      (node (ref "IC1") (pin "5") (pinfunction "+IN_5") (pintype "input"))
      (node (ref "IC2") (pin "3") (pinfunction "+IN_3") (pintype "input"))
      (node (ref "IC3") (pin "12") (pinfunction "+IN_12") (pintype "input"))
      (node (ref "IC3") (pin "5") (pinfunction "+IN_5") (pintype "input"))
      (node (ref "IC4") (pin "14") (pinfunction "IN_P_14") (pintype "input"))
      (node (ref "IC4") (pin "3") (pinfunction "IN_P_3") (pintype "input"))
      (node (ref "IC5") (pin "14") (pinfunction "IN_P_14") (pintype "input"))
      (node (ref "IC5") (pin "3") (pinfunction "IN_P_3") (pintype "input"))
      (node (ref "IC6") (pin "14") (pinfunction "IN_P_14") (pintype "input"))
      (node (ref "IC6") (pin "3") (pinfunction "IN_P_3") (pintype "input"))
      (node (ref "IC7") (pin "15") (pinfunction "GND_15") (pintype "power_in"))
      (node (ref "IC8") (pin "11") (pinfunction "I_11") (pintype "input"))
      (node (ref "IC8") (pin "13") (pinfunction "I_13") (pintype "input"))
      (node (ref "IC8") (pin "5") (pinfunction "I_5") (pintype "input"))
      (node (ref "IC8") (pin "7") (pinfunction "VSS_7") (pintype "power_in"))
      (node (ref "IC8") (pin "9") (pinfunction "I_9") (pintype "input"))
      (node (ref "IN1") (pin "P1") (pinfunction "1_P1") (pintype "passive"))
      (node (ref "IN2") (pin "P1") (pinfunction "1_P1") (pintype "passive"))
      (node (ref "LED1") (pin "GND") (pinfunction "C_GND") (pintype "bidirectional"))
      (node (ref "LEVEL_1") (pin "P$3") (pinfunction "A_P$3") (pintype "passive"))
      (node (ref "OUT") (pin "P1") (pinfunction "1_P1") (pintype "passive"))
      (node (ref "POWER!") (pin "3") (pinfunction "GND_3") (pintype "bidirectional"))
      (node (ref "POWER!") (pin "4") (pinfunction "GND_4") (pintype "bidirectional"))
      (node (ref "POWER!") (pin "5") (pinfunction "GND_5") (pintype "bidirectional"))
      (node (ref "POWER!") (pin "6") (pinfunction "GND_6") (pintype "bidirectional"))
      (node (ref "POWER!") (pin "7") (pinfunction "GND_7") (pintype "bidirectional"))
      (node (ref "POWER!") (pin "8") (pinfunction "GND_8") (pintype "bidirectional"))
      (node (ref "Q1") (pin "2") (pinfunction "F_2") (pintype "bidirectional"))
      (node (ref "Q2") (pin "2") (pinfunction "F_2") (pintype "bidirectional"))
      (node (ref "R24") (pin "2") (pinfunction "2_2") (pintype "passive"))
      (node (ref "R28") (pin "1") (pinfunction "1_1") (pintype "passive"))
      (node (ref "R37") (pin "1") (pinfunction "1_1") (pintype "passive"))
      (node (ref "R42") (pin "1") (pinfunction "1_1") (pintype "passive"))
      (node (ref "R50") (pin "1") (pinfunction "1_1") (pintype "passive"))
      (node (ref "R53") (pin "1") (pinfunction "1_1") (pintype "passive"))
      (node (ref "R58") (pin "1") (pinfunction "1_1") (pintype "passive"))
      (node (ref "R6") (pin "1") (pinfunction "1_1") (pintype "passive"))
      (node (ref "R66") (pin "1") (pinfunction "1_1") (pintype "passive"))
      (node (ref "R67") (pin "1") (pinfunction "1_1") (pintype "passive"))
      (node (ref "R70") (pin "1") (pinfunction "1_1") (pintype "passive"))
      (node (ref "RES") (pin "P$3") (pinfunction "A_P$3") (pintype "passive"))
      (node (ref "RES_CV") (pin "P1") (pinfunction "1_P1") (pintype "passive"))
      (node (ref "SW1") (pin "B1") (pinfunction "P_B1") (pintype "passive"))
      (node (ref "SW1") (pin "B2") (pinfunction "P1_B2") (pintype "passive"))
      (node (ref "U1") (pin "3") (pinfunction "+IN_3") (pintype "input"))
      (node (ref "U2") (pin "3") (pinfunction "+IN_3") (pintype "input"))
      (node (ref "U3") (pin "7") (pinfunction "SET2_7") (pintype "passive"))
      (node (ref "U3") (pin "8") (pinfunction "VSS_8") (pintype "power_in"))
      (node (ref "U3") (pin "9") (pinfunction "SET1_9") (pintype "passive"))
      (node (ref "U4") (pin "6") (pinfunction "INH_6") (pintype "input"))
      (node (ref "U4") (pin "7") (pinfunction "VEE_7") (pintype "power_in"))
      (node (ref "U4") (pin "8") (pinfunction "VSS_8") (pintype "power_in"))
    )
    (net (code "8") (name "LED_BLU") (class "Default")
      (node (ref "LED1") (pin "BLU") (pinfunction "BLU_BLU") (pintype "bidirectional"))
      (node (ref "U4") (pin "11") (pinfunction "3_2_11") (pintype "bidirectional"))
      (node (ref "U4") (pin "14") (pinfunction "1_2_14") (pintype "bidirectional"))
    )
    (net (code "9") (name "LED_GRN") (class "Default")
      (node (ref "LED1") (pin "GRN") (pinfunction "GRN_GRN") (pintype "bidirectional"))
      (node (ref "U4") (pin "2") (pinfunction "2_2") (pintype "input"))
    )
    (net (code "10") (name "LED_RED") (class "Default")
      (node (ref "LED1") (pin "RED") (pinfunction "RED_RED") (pintype "bidirectional"))
      (node (ref "U4") (pin "1") (pinfunction "0_1") (pintype "input"))
      (node (ref "U4") (pin "5") (pinfunction "1_5") (pintype "bidirectional"))
    )
    (net (code "11") (name "Net-(C5-Pad+)") (class "Default")
      (node (ref "C5") (pin "+") (pinfunction "+_+") (pintype "passive"))
      (node (ref "R8") (pin "1") (pinfunction "1_1") (pintype "passive"))
    )
    (net (code "12") (name "Net-(C31-Pad1)") (class "Default")
      (node (ref "C31") (pin "1") (pinfunction "1_1") (pintype "passive"))
      (node (ref "D6") (pin "A") (pinfunction "A_A") (pintype "passive"))
      (node (ref "R74") (pin "2") (pinfunction "2_2") (pintype "passive"))
      (node (ref "R77") (pin "2") (pinfunction "2_2") (pintype "passive"))
    )
    (net (code "13") (name "Net-(CV1-3)") (class "Default")
      (node (ref "CV1") (pin "P3") (pinfunction "3_P3") (pintype "passive"))
      (node (ref "FM_1") (pin "P$1") (pinfunction "E_P$1") (pintype "passive"))
      (node (ref "R32") (pin "2") (pinfunction "2_2") (pintype "passive"))
    )
    (net (code "14") (name "Net-(CV2-3)") (class "Default")
      (node (ref "CV2") (pin "P3") (pinfunction "3_P3") (pintype "passive"))
      (node (ref "FM_2") (pin "P$1") (pinfunction "E_P$1") (pintype "passive"))
    )
    (net (code "15") (name "Net-(D4-PadC)") (class "Default")
      (node (ref "D4") (pin "C") (pinfunction "C_C") (pintype "passive"))
      (node (ref "D5") (pin "A") (pinfunction "A_A") (pintype "passive"))
      (node (ref "R67") (pin "2") (pinfunction "2_2") (pintype "passive"))
      (node (ref "R68") (pin "2") (pinfunction "2_2") (pintype "passive"))
    )
    (net (code "16") (name "Net-(FM_1-S)") (class "Default")
      (node (ref "FM_1") (pin "P$2") (pinfunction "S_P$2") (pintype "passive"))
      (node (ref "IC3") (pin "3") (pinfunction "+IN_3") (pintype "input"))
    )
    (net (code "17") (name "Net-(FM_2-S)") (class "Default")
      (node (ref "FM_2") (pin "P$2") (pinfunction "S_P$2") (pintype "passive"))
      (node (ref "R27") (pin "2") (pinfunction "2_2") (pintype "passive"))
    )
    (net (code "18") (name "Net-(FREQ-S)") (class "Default")
      (node (ref "FREQ") (pin "P$2") (pinfunction "S_P$2") (pintype "passive"))
      (node (ref "R48") (pin "2") (pinfunction "2_2") (pintype "passive"))
    )
    (net (code "19") (name "Net-(IC1A--IN)") (class "Default")
      (node (ref "C12") (pin "1") (pinfunction "1_1") (pintype "passive"))
      (node (ref "IC1") (pin "2") (pinfunction "-IN_2") (pintype "input"))
      (node (ref "R7") (pin "1") (pinfunction "1_1") (pintype "passive"))
      (node (ref "R8") (pin "2") (pinfunction "2_2") (pintype "passive"))
    )
    (net (code "20") (name "Net-(IC1B--IN)") (class "Default")
      (node (ref "D3") (pin "C") (pinfunction "C_C") (pintype "passive"))
      (node (ref "IC1") (pin "6") (pinfunction "-IN_6") (pintype "input"))
      (node (ref "R18") (pin "1") (pinfunction "1_1") (pintype "passive"))
      (node (ref "R19") (pin "2") (pinfunction "2_2") (pintype "passive"))
    )
    (net (code "21") (name "Net-(IC1B-OUT)") (class "Default")
      (node (ref "D3") (pin "A") (pinfunction "A_A") (pintype "passive"))
      (node (ref "IC1") (pin "7") (pinfunction "OUT_7") (pintype "output"))
      (node (ref "R17") (pin "2") (pinfunction "2_2") (pintype "passive"))
      (node (ref "R18") (pin "2") (pinfunction "2_2") (pintype "passive"))
    )
    (net (code "22") (name "Net-(IC2A--IN)") (class "Default")
      (node (ref "C10") (pin "2") (pinfunction "2_2") (pintype "passive"))
      (node (ref "IC2") (pin "2") (pinfunction "-IN_2") (pintype "input"))
      (node (ref "R1") (pin "2") (pinfunction "2_2") (pintype "passive"))
      (node (ref "R3") (pin "2") (pinfunction "2_2") (pintype "passive"))
      (node (ref "R4") (pin "1") (pinfunction "1_1") (pintype "passive"))
    )
    (net (code "23") (name "Net-(IC2A-OUT)") (class "Default")
      (node (ref "C10") (pin "1") (pinfunction "1_1") (pintype "passive"))
      (node (ref "IC2") (pin "1") (pinfunction "OUT_1") (pintype "output"))
      (node (ref "R13") (pin "2") (pinfunction "2_2") (pintype "passive"))
      (node (ref "R4") (pin "2") (pinfunction "2_2") (pintype "passive"))
      (node (ref "R5") (pin "1") (pinfunction "1_1") (pintype "passive"))
    )
    (net (code "24") (name "Net-(IC2B-+IN)") (class "Default")
      (node (ref "C11") (pin "1") (pinfunction "1_1") (pintype "passive"))
      (node (ref "IC2") (pin "5") (pinfunction "+IN_5") (pintype "input"))
      (node (ref "R5") (pin "2") (pinfunction "2_2") (pintype "passive"))
      (node (ref "R6") (pin "2") (pinfunction "2_2") (pintype "passive"))
    )
    (net (code "25") (name "Net-(IC2B--IN)") (class "Default")
      (node (ref "C17") (pin "2") (pinfunction "2_2") (pintype "passive"))
      (node (ref "IC2") (pin "6") (pinfunction "-IN_6") (pintype "input"))
      (node (ref "IC4") (pin "12") (pinfunction "OUT_12") (pintype "output"))
      (node (ref "R14") (pin "1") (pinfunction "1_1") (pintype "passive"))
      (node (ref "R9") (pin "1") (pinfunction "1_1") (pintype "passive"))
    )
    (net (code "26") (name "Net-(IC2B-OUT)") (class "Default")
      (node (ref "IC2") (pin "7") (pinfunction "OUT_7") (pintype "output"))
      (node (ref "R35") (pin "1") (pinfunction "1_1") (pintype "passive"))
      (node (ref "R41") (pin "1") (pinfunction "1_1") (pintype "passive"))
      (node (ref "R9") (pin "2") (pinfunction "2_2") (pintype "passive"))
    )
    (net (code "27") (name "Net-(IC3A--IN)") (class "Default")
      (node (ref "IC3") (pin "2") (pinfunction "-IN_2") (pintype "input"))
      (node (ref "R32") (pin "1") (pinfunction "1_1") (pintype "passive"))
      (node (ref "R34") (pin "2") (pinfunction "2_2") (pintype "passive"))
    )
    (net (code "28") (name "Net-(IC3A-OUT)") (class "Default")
      (node (ref "IC3") (pin "1") (pinfunction "OUT_1") (pintype "output"))
      (node (ref "R34") (pin "1") (pinfunction "1_1") (pintype "passive"))
      (node (ref "R45") (pin "2") (pinfunction "2_2") (pintype "passive"))
    )
    (net (code "29") (name "Net-(IC3B--IN)") (class "Default")
      (node (ref "C16") (pin "2") (pinfunction "2_2") (pintype "passive"))
      (node (ref "IC3") (pin "6") (pinfunction "-IN_6") (pintype "input"))
      (node (ref "R11") (pin "1") (pinfunction "1_1") (pintype "passive"))
      (node (ref "R17") (pin "1") (pinfunction "1_1") (pintype "passive"))
      (node (ref "R36") (pin "1") (pinfunction "1_1") (pintype "passive"))
    )
    (net (code "30") (name "Net-(IC3B-OUT)") (class "Default")
      (node (ref "C16") (pin "1") (pinfunction "1_1") (pintype "passive"))
      (node (ref "IC3") (pin "7") (pinfunction "OUT_7") (pintype "output"))
      (node (ref "R11") (pin "2") (pinfunction "2_2") (pintype "passive"))
      (node (ref "R29") (pin "1") (pinfunction "1_1") (pintype "passive"))
    )
    (net (code "31") (name "Net-(IC3C-+IN)") (class "Default")
      (node (ref "C29") (pin "1") (pinfunction "1_1") (pintype "passive"))
      (node (ref "D4") (pin "A") (pinfunction "A_A") (pintype "passive"))
      (node (ref "D5") (pin "C") (pinfunction "C_C") (pintype "passive"))
      (node (ref "IC3") (pin "10") (pinfunction "+IN_10") (pintype "input"))
      (node (ref "R69") (pin "2") (pinfunction "2_2") (pintype "passive"))
      (node (ref "R70") (pin "2") (pinfunction "2_2") (pintype "passive"))
    )
    (net (code "32") (name "Net-(IC3C--IN)") (class "Default")
      (node (ref "C28") (pin "2") (pinfunction "2_2") (pintype "passive"))
      (node (ref "IC3") (pin "9") (pinfunction "-IN_9") (pintype "input"))
      (node (ref "IC4") (pin "5") (pinfunction "OUT_5") (pintype "output"))
      (node (ref "R62") (pin "1") (pinfunction "1_1") (pintype "passive"))
      (node (ref "R64") (pin "1") (pinfunction "1_1") (pintype "passive"))
    )
    (net (code "33") (name "Net-(IC3C-OUT)") (class "Default")
      (node (ref "IC3") (pin "8") (pinfunction "OUT_8") (pintype "output"))
      (node (ref "R63") (pin "1") (pinfunction "1_1") (pintype "passive"))
      (node (ref "R64") (pin "2") (pinfunction "2_2") (pintype "passive"))
      (node (ref "R65") (pin "1") (pinfunction "1_1") (pintype "passive"))
    )
    (net (code "34") (name "Net-(IC3D--IN)") (class "Default")
      (node (ref "C24") (pin "2") (pinfunction "2_2") (pintype "passive"))
      (node (ref "IC3") (pin "13") (pinfunction "-IN_13") (pintype "input"))
      (node (ref "R27") (pin "1") (pinfunction "1_1") (pintype "passive"))
      (node (ref "R45") (pin "1") (pinfunction "1_1") (pintype "passive"))
      (node (ref "R46") (pin "2") (pinfunction "2_2") (pintype "passive"))
      (node (ref "R47") (pin "1") (pinfunction "1_1") (pintype "passive"))
      (node (ref "R48") (pin "1") (pinfunction "1_1") (pintype "passive"))
      (node (ref "R49") (pin "2") (pinfunction "2_2") (pintype "passive"))
    )
    (net (code "35") (name "Net-(IC3D-OUT)") (class "Default")
      (node (ref "C24") (pin "1") (pinfunction "1_1") (pintype "passive"))
      (node (ref "IC3") (pin "14") (pinfunction "OUT_14") (pintype "output"))
      (node (ref "R33") (pin "2") (pinfunction "2_2") (pintype "passive"))
      (node (ref "R49") (pin "1") (pinfunction "1_1") (pintype "passive"))
    )
    (net (code "36") (name "Net-(IC4C-IN_N)") (class "Default")
      (node (ref "IC4") (pin "4") (pinfunction "IN_N_4") (pintype "input"))
      (node (ref "R37") (pin "2") (pinfunction "2_2") (pintype "passive"))
      (node (ref "R39") (pin "2") (pinfunction "2_2") (pintype "passive"))
    )
    (net (code "37") (name "Net-(IC4C-I_BIAS)") (class "Default")
      (node (ref "IC4") (pin "1") (pinfunction "I_BIAS_1") (pintype "input"))
      (node (ref "R40") (pin "1") (pinfunction "1_1") (pintype "passive"))
    )
    (net (code "38") (name "Net-(IC4D-IN_N)") (class "Default")
      (node (ref "IC4") (pin "13") (pinfunction "IN_N_13") (pintype "input"))
      (node (ref "R13") (pin "1") (pinfunction "1_1") (pintype "passive"))
      (node (ref "R50") (pin "2") (pinfunction "2_2") (pintype "passive"))
      (node (ref "R54") (pin "2") (pinfunction "2_2") (pintype "passive"))
    )
    (net (code "39") (name "Net-(IC4D-I_BIAS)") (class "Default")
      (node (ref "IC4") (pin "16") (pinfunction "I_BIAS_16") (pintype "input"))
      (node (ref "R51") (pin "1") (pinfunction "1_1") (pintype "passive"))
    )
    (net (code "40") (name "Net-(IC5C-IN_N)") (class "Default")
      (node (ref "IC5") (pin "4") (pinfunction "IN_N_4") (pintype "input"))
      (node (ref "R41") (pin "2") (pinfunction "2_2") (pintype "passive"))
      (node (ref "R42") (pin "2") (pinfunction "2_2") (pintype "passive"))
    )
    (net (code "41") (name "Net-(IC5C-I_BIAS)") (class "Default")
      (node (ref "IC5") (pin "1") (pinfunction "I_BIAS_1") (pintype "input"))
      (node (ref "R43") (pin "1") (pinfunction "1_1") (pintype "passive"))
    )
    (net (code "42") (name "Net-(IC5C-OUT)") (class "Default")
      (node (ref "C1") (pin "1") (pinfunction "1_1") (pintype "passive"))
      (node (ref "IC5") (pin "5") (pinfunction "OUT_5") (pintype "output"))
      (node (ref "Q4") (pin "3") (pinfunction "P$3_3") (pintype "bidirectional"))
    )
    (net (code "43") (name "Net-(IC5D-IN_N)") (class "Default")
      (node (ref "IC5") (pin "13") (pinfunction "IN_N_13") (pintype "input"))
      (node (ref "R52") (pin "2") (pinfunction "2_2") (pintype "passive"))
      (node (ref "R53") (pin "2") (pinfunction "2_2") (pintype "passive"))
    )
    (net (code "44") (name "Net-(IC5D-I_BIAS)") (class "Default")
      (node (ref "IC5") (pin "16") (pinfunction "I_BIAS_16") (pintype "input"))
      (node (ref "R44") (pin "1") (pinfunction "1_1") (pintype "passive"))
    )
    (net (code "45") (name "Net-(IC5D-OUT)") (class "Default")
      (node (ref "C3") (pin "1") (pinfunction "1_1") (pintype "passive"))
      (node (ref "IC5") (pin "12") (pinfunction "OUT_12") (pintype "output"))
      (node (ref "Q3") (pin "3") (pinfunction "P$3_3") (pintype "bidirectional"))
    )
    (net (code "46") (name "Net-(IC6C-IN_N)") (class "Default")
      (node (ref "IC6") (pin "4") (pinfunction "IN_N_4") (pintype "input"))
      (node (ref "R57") (pin "1") (pinfunction "1_1") (pintype "passive"))
      (node (ref "R58") (pin "2") (pinfunction "2_2") (pintype "passive"))
    )
    (net (code "47") (name "Net-(IC6C-I_BIAS)") (class "Default")
      (node (ref "IC6") (pin "1") (pinfunction "I_BIAS_1") (pintype "input"))
      (node (ref "R59") (pin "1") (pinfunction "1_1") (pintype "passive"))
    )
    (net (code "48") (name "Net-(IC6C-OUT)") (class "Default")
      (node (ref "C2") (pin "1") (pinfunction "1_1") (pintype "passive"))
      (node (ref "IC6") (pin "5") (pinfunction "OUT_5") (pintype "output"))
      (node (ref "Q5") (pin "3") (pinfunction "P$3_3") (pintype "bidirectional"))
    )
    (net (code "49") (name "Net-(IC6D-IN_N)") (class "Default")
      (node (ref "IC6") (pin "13") (pinfunction "IN_N_13") (pintype "input"))
      (node (ref "R65") (pin "2") (pinfunction "2_2") (pintype "passive"))
      (node (ref "R66") (pin "2") (pinfunction "2_2") (pintype "passive"))
    )
    (net (code "50") (name "Net-(IC6D-I_BIAS)") (class "Default")
      (node (ref "IC6") (pin "16") (pinfunction "I_BIAS_16") (pintype "input"))
      (node (ref "R56") (pin "1") (pinfunction "1_1") (pintype "passive"))
    )
    (net (code "51") (name "Net-(IC6D-OUT)") (class "Default")
      (node (ref "C6") (pin "1") (pinfunction "1_1") (pintype "passive"))
      (node (ref "IC6") (pin "12") (pinfunction "OUT_12") (pintype "output"))
      (node (ref "Q6") (pin "3") (pinfunction "P$3_3") (pintype "bidirectional"))
    )
    (net (code "52") (name "Net-(IC8A-I)") (class "Default")
      (node (ref "IC8") (pin "1") (pinfunction "I_1") (pintype "input"))
      (node (ref "R77") (pin "1") (pinfunction "1_1") (pintype "passive"))
    )
    (net (code "53") (name "Net-(IC8A-O)") (class "Default")
      (node (ref "IC8") (pin "2") (pinfunction "O_2") (pintype "output"))
      (node (ref "U3") (pin "12") (pinfunction "RESET1_12") (pintype "passive"))
      (node (ref "U3") (pin "4") (pinfunction "RESET2_4") (pintype "passive"))
    )
    (net (code "54") (name "Net-(IC8B-I)") (class "Default")
      (node (ref "C30") (pin "1") (pinfunction "1_1") (pintype "passive"))
      (node (ref "IC8") (pin "3") (pinfunction "I_3") (pintype "input"))
      (node (ref "R75") (pin "2") (pinfunction "2_2") (pintype "passive"))
      (node (ref "R76") (pin "2") (pinfunction "2_2") (pintype "passive"))
    )
    (net (code "55") (name "Net-(IC8B-O)") (class "Default")
      (node (ref "IC8") (pin "4") (pinfunction "O_4") (pintype "output"))
      (node (ref "U3") (pin "3") (pinfunction "CLOCK2_3") (pintype "passive"))
    )
    (net (code "56") (name "Net-(IN1-3)") (class "Default")
      (node (ref "IN1") (pin "P3") (pinfunction "3_P3") (pintype "passive"))
      (node (ref "R1") (pin "1") (pinfunction "1_1") (pintype "passive"))
    )
    (net (code "57") (name "Net-(IN2-3)") (class "Default")
      (node (ref "IN2") (pin "P3") (pinfunction "3_P3") (pintype "passive"))
      (node (ref "LEVEL_1") (pin "P$1") (pinfunction "E_P$1") (pintype "passive"))
    )
    (net (code "58") (name "Net-(LEVEL_1-S)") (class "Default")
      (node (ref "LEVEL_1") (pin "P$2") (pinfunction "S_P$2") (pintype "passive"))
      (node (ref "R3") (pin "1") (pinfunction "1_1") (pintype "passive"))
    )
    (net (code "59") (name "Net-(P1-Pad2)") (class "Default")
      (node (ref "P1") (pin "2") (pinfunction "2_2") (pintype "passive"))
      (node (ref "POWER!") (pin "10") (pinfunction "+12V_10") (pintype "bidirectional"))
      (node (ref "POWER!") (pin "9") (pinfunction "+12V_9") (pintype "bidirectional"))
    )
    (net (code "60") (name "Net-(P2-Pad2)") (class "Default")
      (node (ref "P2") (pin "2") (pinfunction "2_2") (pintype "passive"))
      (node (ref "POWER!") (pin "1") (pinfunction "-12V_1") (pintype "bidirectional"))
      (node (ref "POWER!") (pin "2") (pinfunction "-12V_2") (pintype "bidirectional"))
    )
    (net (code "61") (name "Net-(Q1-E)") (class "Default")
      (node (ref "Q1") (pin "1") (pinfunction "E_1") (pintype "bidirectional"))
      (node (ref "Q1") (pin "4") (pinfunction "H_4") (pintype "bidirectional"))
      (node (ref "R12") (pin "1") (pinfunction "1_1") (pintype "passive"))
    )
    (net (code "62") (name "Net-(Q1-I)") (class "Default")
      (node (ref "Q1") (pin "5") (pinfunction "I_5") (pintype "bidirectional"))
      (node (ref "R20") (pin "1") (pinfunction "1_1") (pintype "passive"))
      (node (ref "R21") (pin "1") (pinfunction "1_1") (pintype "passive"))
      (node (ref "R24") (pin "1") (pinfunction "1_1") (pintype "passive"))
    )
    (net (code "63") (name "Net-(Q1-J)") (class "Default")
      (node (ref "C18") (pin "2") (pinfunction "2_2") (pintype "passive"))
      (node (ref "Q1") (pin "6") (pinfunction "J_6") (pintype "bidirectional"))
      (node (ref "R10") (pin "1") (pinfunction "1_1") (pintype "passive"))
      (node (ref "U1") (pin "4") (pinfunction "-IN_4") (pintype "input"))
    )
    (net (code "64") (name "Net-(Q2-E)") (class "Default")
      (node (ref "Q2") (pin "1") (pinfunction "E_1") (pintype "bidirectional"))
      (node (ref "Q2") (pin "4") (pinfunction "H_4") (pintype "bidirectional"))
      (node (ref "R31") (pin "2") (pinfunction "2_2") (pintype "passive"))
    )
    (net (code "65") (name "Net-(Q2-I)") (class "Default")
      (node (ref "Q2") (pin "5") (pinfunction "I_5") (pintype "bidirectional"))
      (node (ref "R23") (pin "2") (pinfunction "2_2") (pintype "passive"))
      (node (ref "R28") (pin "2") (pinfunction "2_2") (pintype "passive"))
      (node (ref "R29") (pin "2") (pinfunction "2_2") (pintype "passive"))
      (node (ref "R30") (pin "2") (pinfunction "2_2") (pintype "passive"))
    )
    (net (code "66") (name "Net-(Q2-J)") (class "Default")
      (node (ref "C19") (pin "2") (pinfunction "2_2") (pintype "passive"))
      (node (ref "Q2") (pin "6") (pinfunction "J_6") (pintype "bidirectional"))
      (node (ref "R16") (pin "2") (pinfunction "2_2") (pintype "passive"))
      (node (ref "U2") (pin "4") (pinfunction "-IN_4") (pintype "input"))
    )
    (net (code "67") (name "Net-(Q3-P$1)") (class "Default")
      (node (ref "C17") (pin "1") (pinfunction "1_1") (pintype "passive"))
      (node (ref "Q3") (pin "1") (pinfunction "P$1_1") (pintype "bidirectional"))
      (node (ref "R14") (pin "2") (pinfunction "2_2") (pintype "passive"))
      (node (ref "R15") (pin "2") (pinfunction "2_2") (pintype "passive"))
      (node (ref "R25") (pin "1") (pinfunction "1_1") (pintype "passive"))
      (node (ref "R26") (pin "1") (pinfunction "1_1") (pintype "passive"))
    )
    (net (code "68") (name "Net-(Q4-P$1)") (class "Default")
      (node (ref "Q4") (pin "1") (pinfunction "P$1_1") (pintype "bidirectional"))
      (node (ref "R52") (pin "1") (pinfunction "1_1") (pintype "passive"))
      (node (ref "R54") (pin "1") (pinfunction "1_1") (pintype "passive"))
      (node (ref "R55") (pin "2") (pinfunction "2_2") (pintype "passive"))
    )
    (net (code "69") (name "Net-(Q5-P$1)") (class "Default")
      (node (ref "C28") (pin "1") (pinfunction "1_1") (pintype "passive"))
      (node (ref "Q5") (pin "1") (pinfunction "P$1_1") (pintype "bidirectional"))
      (node (ref "R60") (pin "1") (pinfunction "1_1") (pintype "passive"))
      (node (ref "R61") (pin "2") (pinfunction "2_2") (pintype "passive"))
      (node (ref "R62") (pin "2") (pinfunction "2_2") (pintype "passive"))
    )
    (net (code "70") (name "Net-(Q6-P$1)") (class "Default")
      (node (ref "Q6") (pin "1") (pinfunction "P$1_1") (pintype "bidirectional"))
      (node (ref "R38") (pin "2") (pinfunction "2_2") (pintype "passive"))
      (node (ref "R39") (pin "1") (pinfunction "1_1") (pintype "passive"))
      (node (ref "R57") (pin "2") (pinfunction "2_2") (pintype "passive"))
      (node (ref "R68") (pin "1") (pinfunction "1_1") (pintype "passive"))
    )
    (net (code "71") (name "Net-(R20-Pad2)") (class "Default")
      (node (ref "R20") (pin "2") (pinfunction "2_2") (pintype "passive"))
      (node (ref "R22") (pin "2") (pinfunction "2_2") (pintype "passive"))
      (node (ref "R33") (pin "1") (pinfunction "1_1") (pintype "passive"))
    )
    (net (code "72") (name "Net-(R21-Pad2)") (class "Default")
      (node (ref "R21") (pin "2") (pinfunction "2_2") (pintype "passive"))
      (node (ref "R22") (pin "1") (pinfunction "1_1") (pintype "passive"))
    )
    (net (code "73") (name "Net-(RES-E)") (class "Default")
      (node (ref "R73") (pin "2") (pinfunction "2_2") (pintype "passive"))
      (node (ref "RES") (pin "P$1") (pinfunction "E_P$1") (pintype "passive"))
    )
    (net (code "74") (name "Net-(RES-S)") (class "Default")
      (node (ref "R36") (pin "2") (pinfunction "2_2") (pintype "passive"))
      (node (ref "RES") (pin "P$2") (pinfunction "S_P$2") (pintype "passive"))
    )
    (net (code "75") (name "Net-(RES_CV-3)") (class "Default")
      (node (ref "R19") (pin "1") (pinfunction "1_1") (pintype "passive"))
      (node (ref "RES_CV") (pin "P3") (pinfunction "3_P3") (pintype "passive"))
    )
    (net (code "76") (name "Net-(SW1-S)") (class "Default")
      (node (ref "R76") (pin "1") (pinfunction "1_1") (pintype "passive"))
      (node (ref "SW1") (pin "A1") (pinfunction "S_A1") (pintype "passive"))
      (node (ref "SW1") (pin "A2") (pinfunction "S1_A2") (pintype "passive"))
    )
    (net (code "77") (name "Net-(TR1-P$2)") (class "Default")
      (node (ref "R47") (pin "2") (pinfunction "2_2") (pintype "passive"))
      (node (ref "TR1") (pin "2") (pinfunction "P$2_2") (pintype "bidirectional"))
    )
    (net (code "78") (name "Net-(TR2-P$2)") (class "Default")
      (node (ref "R30") (pin "1") (pinfunction "1_1") (pintype "passive"))
      (node (ref "TR2") (pin "2") (pinfunction "P$2_2") (pintype "bidirectional"))
    )
    (net (code "79") (name "Net-(U1-OUT)") (class "Default")
      (node (ref "C18") (pin "1") (pinfunction "1_1") (pintype "passive"))
      (node (ref "R12") (pin "2") (pinfunction "2_2") (pintype "passive"))
      (node (ref "U1") (pin "1") (pinfunction "OUT_1") (pintype "output"))
    )
    (net (code "80") (name "Net-(U2-OUT)") (class "Default")
      (node (ref "C19") (pin "1") (pinfunction "1_1") (pintype "passive"))
      (node (ref "R31") (pin "1") (pinfunction "1_1") (pintype "passive"))
      (node (ref "U2") (pin "1") (pinfunction "OUT_1") (pintype "output"))
    )
    (net (code "81") (name "Net-(U3-CLOCK1)") (class "Default")
      (node (ref "U3") (pin "13") (pinfunction "CLOCK1_13") (pintype "passive"))
      (node (ref "U3") (pin "2") (pinfunction "~{Q2}_2") (pintype "output"))
    )
    (net (code "82") (name "Net-(U4-COMMON)") (class "Default")
      (node (ref "R71") (pin "2") (pinfunction "2_2") (pintype "passive"))
      (node (ref "U4") (pin "13") (pinfunction "COMMON_13") (pintype "bidirectional"))
    )
    (net (code "83") (name "Net-(U4-COMMON_2)") (class "Default")
      (node (ref "R72") (pin "2") (pinfunction "2_2") (pintype "passive"))
      (node (ref "U4") (pin "3") (pinfunction "COMMON_2_3") (pintype "bidirectional"))
    )
    (net (code "84") (name "OUT2A") (class "Default")
      (node (ref "IC7") (pin "4") (pinfunction "S1A_4") (pintype "passive"))
      (node (ref "IC7") (pin "5") (pinfunction "S2A_5") (pintype "passive"))
      (node (ref "R26") (pin "2") (pinfunction "2_2") (pintype "passive"))
    )
    (net (code "85") (name "OUT2B") (class "Default")
      (node (ref "IC7") (pin "12") (pinfunction "S2B_12") (pintype "passive"))
      (node (ref "R25") (pin "2") (pinfunction "2_2") (pintype "passive"))
    )
    (net (code "86") (name "OUT4") (class "Default")
      (node (ref "IC7") (pin "11") (pinfunction "S3B_11") (pintype "passive"))
      (node (ref "IC7") (pin "13") (pinfunction "S1B_13") (pintype "passive"))
      (node (ref "R60") (pin "2") (pinfunction "2_2") (pintype "passive"))
    )
    (net (code "87") (name "OUTPUT") (class "Default")
      (node (ref "OUT") (pin "P3") (pinfunction "3_P3") (pintype "passive"))
      (node (ref "R2") (pin "2") (pinfunction "2_2") (pintype "passive"))
    )
    (net (code "88") (name "RES_CTRL") (class "Default")
      (node (ref "Q2") (pin "3") (pinfunction "G_3") (pintype "bidirectional"))
      (node (ref "R40") (pin "2") (pinfunction "2_2") (pintype "passive"))
      (node (ref "R51") (pin "2") (pinfunction "2_2") (pintype "passive"))
    )
    (net (code "89") (name "SUM1") (class "Default")
      (node (ref "IC7") (pin "6") (pinfunction "S3A_6") (pintype "passive"))
      (node (ref "IC7") (pin "7") (pinfunction "S4A_7") (pintype "passive"))
      (node (ref "R35") (pin "2") (pinfunction "2_2") (pintype "passive"))
    )
    (net (code "90") (name "SUM2") (class "Default")
      (node (ref "IC7") (pin "10") (pinfunction "S4B_10") (pintype "passive"))
      (node (ref "R63") (pin "2") (pinfunction "2_2") (pintype "passive"))
    )
    (net (code "91") (name "SWX1") (class "Default")
      (node (ref "IC7") (pin "8") (pinfunction "DA_8") (pintype "passive"))
      (node (ref "R69") (pin "1") (pinfunction "1_1") (pintype "passive"))
    )
    (net (code "92") (name "SWY2") (class "Default")
      (node (ref "C5") (pin "-") (pinfunction "-_-") (pintype "passive"))
      (node (ref "IC7") (pin "9") (pinfunction "DB_9") (pintype "passive"))
    )
    (net (code "93") (name "unconnected-(CV1-2-PadP2)") (class "Default")
      (node (ref "CV1") (pin "P2") (pinfunction "2_P2") (pintype "passive"))
    )
    (net (code "94") (name "unconnected-(CV2-2-PadP2)") (class "Default")
      (node (ref "CV2") (pin "P2") (pinfunction "2_P2") (pintype "passive"))
    )
    (net (code "95") (name "unconnected-(IC4A-B-Pad7)") (class "Default")
      (node (ref "IC4") (pin "7") (pinfunction "B_7") (pintype "passive"))
    )
    (net (code "96") (name "unconnected-(IC4A-E-Pad8)") (class "Default")
      (node (ref "IC4") (pin "8") (pinfunction "E_8") (pintype "passive"))
    )
    (net (code "97") (name "unconnected-(IC4B-B-Pad10)") (class "Default")
      (node (ref "IC4") (pin "10") (pinfunction "B_10") (pintype "passive"))
    )
    (net (code "98") (name "unconnected-(IC4B-E-Pad9)") (class "Default")
      (node (ref "IC4") (pin "9") (pinfunction "E_9") (pintype "passive"))
    )
    (net (code "99") (name "unconnected-(IC4C-I_DIODE-Pad2)") (class "Default")
      (node (ref "IC4") (pin "2") (pinfunction "I_DIODE_2") (pintype "input"))
    )
    (net (code "100") (name "unconnected-(IC4D-I_DIODE-Pad15)") (class "Default")
      (node (ref "IC4") (pin "15") (pinfunction "I_DIODE_15") (pintype "input"))
    )
    (net (code "101") (name "unconnected-(IC5A-B-Pad7)") (class "Default")
      (node (ref "IC5") (pin "7") (pinfunction "B_7") (pintype "passive"))
    )
    (net (code "102") (name "unconnected-(IC5A-E-Pad8)") (class "Default")
      (node (ref "IC5") (pin "8") (pinfunction "E_8") (pintype "passive"))
    )
    (net (code "103") (name "unconnected-(IC5B-B-Pad10)") (class "Default")
      (node (ref "IC5") (pin "10") (pinfunction "B_10") (pintype "passive"))
    )
    (net (code "104") (name "unconnected-(IC5B-E-Pad9)") (class "Default")
      (node (ref "IC5") (pin "9") (pinfunction "E_9") (pintype "passive"))
    )
    (net (code "105") (name "unconnected-(IC5C-I_DIODE-Pad2)") (class "Default")
      (node (ref "IC5") (pin "2") (pinfunction "I_DIODE_2") (pintype "input"))
    )
    (net (code "106") (name "unconnected-(IC5D-I_DIODE-Pad15)") (class "Default")
      (node (ref "IC5") (pin "15") (pinfunction "I_DIODE_15") (pintype "input"))
    )
    (net (code "107") (name "unconnected-(IC6A-B-Pad7)") (class "Default")
      (node (ref "IC6") (pin "7") (pinfunction "B_7") (pintype "passive"))
    )
    (net (code "108") (name "unconnected-(IC6A-E-Pad8)") (class "Default")
      (node (ref "IC6") (pin "8") (pinfunction "E_8") (pintype "passive"))
    )
    (net (code "109") (name "unconnected-(IC6B-B-Pad10)") (class "Default")
      (node (ref "IC6") (pin "10") (pinfunction "B_10") (pintype "passive"))
    )
    (net (code "110") (name "unconnected-(IC6B-E-Pad9)") (class "Default")
      (node (ref "IC6") (pin "9") (pinfunction "E_9") (pintype "passive"))
    )
    (net (code "111") (name "unconnected-(IC6C-I_DIODE-Pad2)") (class "Default")
      (node (ref "IC6") (pin "2") (pinfunction "I_DIODE_2") (pintype "input"))
    )
    (net (code "112") (name "unconnected-(IC6D-I_DIODE-Pad15)") (class "Default")
      (node (ref "IC6") (pin "15") (pinfunction "I_DIODE_15") (pintype "input"))
    )
    (net (code "113") (name "unconnected-(IC8C-O-Pad6)") (class "Default")
      (node (ref "IC8") (pin "6") (pinfunction "O_6") (pintype "output"))
    )
    (net (code "114") (name "unconnected-(IC8D-O-Pad8)") (class "Default")
      (node (ref "IC8") (pin "8") (pinfunction "O_8") (pintype "output"))
    )
    (net (code "115") (name "unconnected-(IC8E-O-Pad10)") (class "Default")
      (node (ref "IC8") (pin "10") (pinfunction "O_10") (pintype "output"))
    )
    (net (code "116") (name "unconnected-(IC8F-O-Pad12)") (class "Default")
      (node (ref "IC8") (pin "12") (pinfunction "O_12") (pintype "output"))
    )
    (net (code "117") (name "unconnected-(IN1-2-PadP2)") (class "Default")
      (node (ref "IN1") (pin "P2") (pinfunction "2_P2") (pintype "passive"))
    )
    (net (code "118") (name "unconnected-(OUT-2-PadP2)") (class "Default")
      (node (ref "OUT") (pin "P2") (pinfunction "2_P2") (pintype "passive"))
    )
    (net (code "119") (name "unconnected-(RES_CV-2-PadP2)") (class "Default")
      (node (ref "RES_CV") (pin "P2") (pinfunction "2_P2") (pintype "passive"))
    )
    (net (code "120") (name "unconnected-(U3-~{Q1}-Pad14)") (class "Default")
      (node (ref "U3") (pin "14") (pinfunction "~{Q1}_14") (pintype "output"))
    )
    (net (code "121") (name "unconnected-(U4-0_2-Pad12)") (class "Default")
      (node (ref "U4") (pin "12") (pinfunction "0_2_12") (pintype "bidirectional"))
    )
    (net (code "122") (name "unconnected-(U4-2_2-Pad15)") (class "Default")
      (node (ref "U4") (pin "15") (pinfunction "2_2_15") (pintype "bidirectional"))
    )
    (net (code "123") (name "unconnected-(U4-3-Pad4)") (class "Default")
      (node (ref "U4") (pin "4") (pinfunction "3_4") (pintype "bidirectional"))
    )
  )
)
